# 5x_Piezo_Hoeller_DS.net
KiCad netlist of a schematic drawn in EAGLE
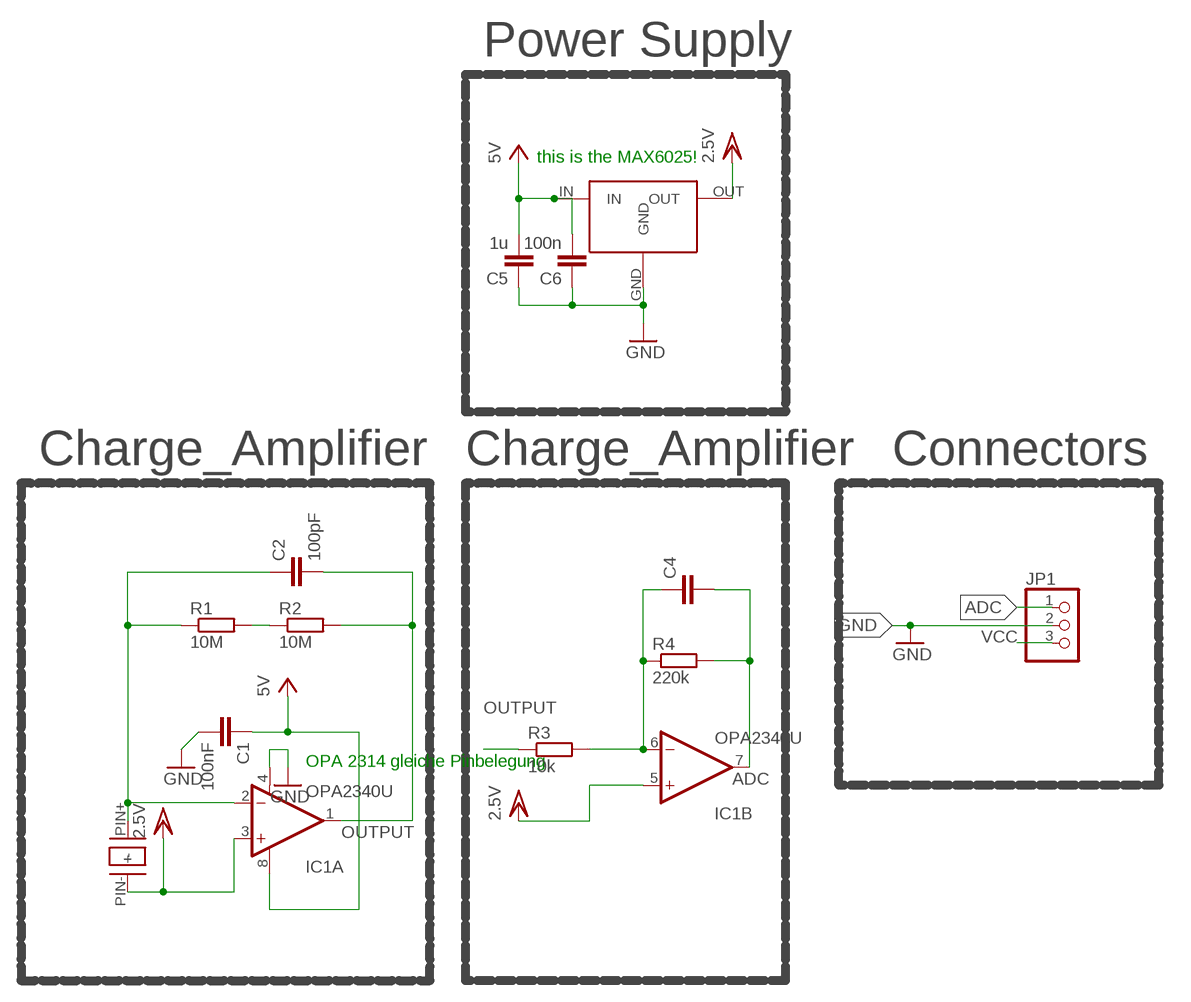
[diagram p0: schematic, sheet 1]

(export (version "E")
  (design (tool "Eeschema 10.0.6"))
  (components
    (comp (ref "C1")
      (value "100nF")
      (footprint "eagle-import:C0603")
      (libsource (lib "eagle-import") (part "C-EUC0603"))
    )
    (comp (ref "C2")
      (value "100pF")
      (footprint "eagle-import:C0603")
      (libsource (lib "eagle-import") (part "C-EUC0603"))
    )
    (comp (ref "C4")
      (value "C-EUC0603")
      (footprint "eagle-import:C0603")
      (libsource (lib "eagle-import") (part "rcl_334_C-EUC0603"))
    )
    (comp (ref "C5")
      (value "1u")
      (footprint "eagle-import:C0603")
      (libsource (lib "eagle-import") (part "C-EUC0603"))
    )
    (comp (ref "C6")
      (value "100n")
      (footprint "eagle-import:C0603")
      (libsource (lib "eagle-import") (part "C-EUC0603"))
    )
    (comp (ref "IC1")
      (value "OPA2340U")
      (footprint "eagle-import:SO08")
      (fields (field (name "MF") "TEXAS INSTRUMENTS") (field (name "MPN") "OPA2340UA"))
      (libsource (lib "eagle-import") (part "OPA2340U"))
    )
    (comp (ref "JP1")
      (value "PINHD-1X3")
      (footprint "eagle-import:1X03")
      (libsource (lib "eagle-import") (part "PINHD-1X3"))
    )
    (comp (ref "R1")
      (value "10M")
      (footprint "eagle-import:R0603")
      (libsource (lib "eagle-import") (part "R-EU_R0603"))
    )
    (comp (ref "R2")
      (value "10M")
      (footprint "eagle-import:R0603")
      (libsource (lib "eagle-import") (part "R-EU_R0603"))
    )
    (comp (ref "R3")
      (value "10k")
      (footprint "eagle-import:R0603")
      (libsource (lib "eagle-import") (part "R-EU_R0603"))
    )
    (comp (ref "R4")
      (value "220k")
      (footprint "eagle-import:R0603")
      (libsource (lib "eagle-import") (part "R-EU_R0603"))
    )
    (comp (ref "U$1")
      (value "MAX6018X")
      (footprint "eagle-import:SOT-3")
      (libsource (lib "eagle-import") (part "MAX6018X"))
    )
    (comp (ref "U$2")
      (value "10MMSCHEIBE")
      (footprint "eagle-import:10MM_SCHEIBE")
      (libsource (lib "eagle-import") (part "10MMSCHEIBE"))
    )
  )
  (nets
    (net (code "1") (name "/OUTPUT") (class "Default")
      (node (ref "C2") (pin "2") (pinfunction "2_2") (pintype "passive"))
      (node (ref "IC1") (pin "1") (pinfunction "OUT_1") (pintype "output"))
      (node (ref "R2") (pin "2") (pinfunction "2_2") (pintype "passive"))
      (node (ref "R3") (pin "1") (pinfunction "1_1") (pintype "passive"))
    )
    (net (code "2") (name "2.5V") (class "Default")
      (node (ref "IC1") (pin "3") (pinfunction "+IN_3") (pintype "input"))
      (node (ref "IC1") (pin "5") (pinfunction "+IN_5") (pintype "input"))
      (node (ref "U$1") (pin "OUT") (pinfunction "OUT_OUT") (pintype "bidirectional"))
      (node (ref "U$2") (pin "PIN-") (pinfunction "-_PIN-") (pintype "bidirectional"))
    )
    (net (code "3") (name "5V") (class "Default")
      (node (ref "C1") (pin "1") (pinfunction "1_1") (pintype "passive"))
      (node (ref "C5") (pin "2") (pinfunction "2_2") (pintype "passive"))
      (node (ref "C6") (pin "2") (pinfunction "2_2") (pintype "passive"))
      (node (ref "IC1") (pin "8") (pinfunction "V+_8") (pintype "power_in"))
      (node (ref "JP1") (pin "3") (pinfunction "3_3") (pintype "passive"))
      (node (ref "U$1") (pin "IN") (pinfunction "IN_IN") (pintype "bidirectional"))
    )
    (net (code "4") (name "ADC") (class "Default")
      (node (ref "C4") (pin "2") (pinfunction "2_2") (pintype "passive"))
      (node (ref "IC1") (pin "7") (pinfunction "OUT_7") (pintype "output"))
      (node (ref "JP1") (pin "1") (pinfunction "1_1") (pintype "passive"))
      (node (ref "R4") (pin "2") (pinfunction "2_2") (pintype "passive"))
    )
    (net (code "5") (name "GND") (class "Default")
      (node (ref "C1") (pin "2") (pinfunction "2_2") (pintype "passive"))
      (node (ref "C5") (pin "1") (pinfunction "1_1") (pintype "passive"))
      (node (ref "C6") (pin "1") (pinfunction "1_1") (pintype "passive"))
      (node (ref "IC1") (pin "4") (pinfunction "V-_4") (pintype "power_in"))
      (node (ref "JP1") (pin "2") (pinfunction "2_2") (pintype "passive"))
      (node (ref "U$1") (pin "GND") (pinfunction "GND_GND") (pintype "bidirectional"))
    )
    (net (code "6") (name "Net-(IC1A--IN)") (class "Default")
      (node (ref "C2") (pin "1") (pinfunction "1_1") (pintype "passive"))
      (node (ref "IC1") (pin "2") (pinfunction "-IN_2") (pintype "input"))
      (node (ref "R1") (pin "1") (pinfunction "1_1") (pintype "passive"))
      (node (ref "U$2") (pin "PIN+") (pinfunction "+_PIN+") (pintype "bidirectional"))
    )
    (net (code "7") (name "Net-(IC1B--IN)") (class "Default")
      (node (ref "C4") (pin "1") (pinfunction "1_1") (pintype "passive"))
      (node (ref "IC1") (pin "6") (pinfunction "-IN_6") (pintype "input"))
      (node (ref "R3") (pin "2") (pinfunction "2_2") (pintype "passive"))
      (node (ref "R4") (pin "1") (pinfunction "1_1") (pintype "passive"))
    )
    (net (code "8") (name "Net-(R1-Pad2)") (class "Default")
      (node (ref "R1") (pin "2") (pinfunction "2_2") (pintype "passive"))
      (node (ref "R2") (pin "1") (pinfunction "1_1") (pintype "passive"))
    )
  )
)
